# HDMI_Connector_for_RK3399.net
KiCad netlist of a schematic drawn in Altium Designer
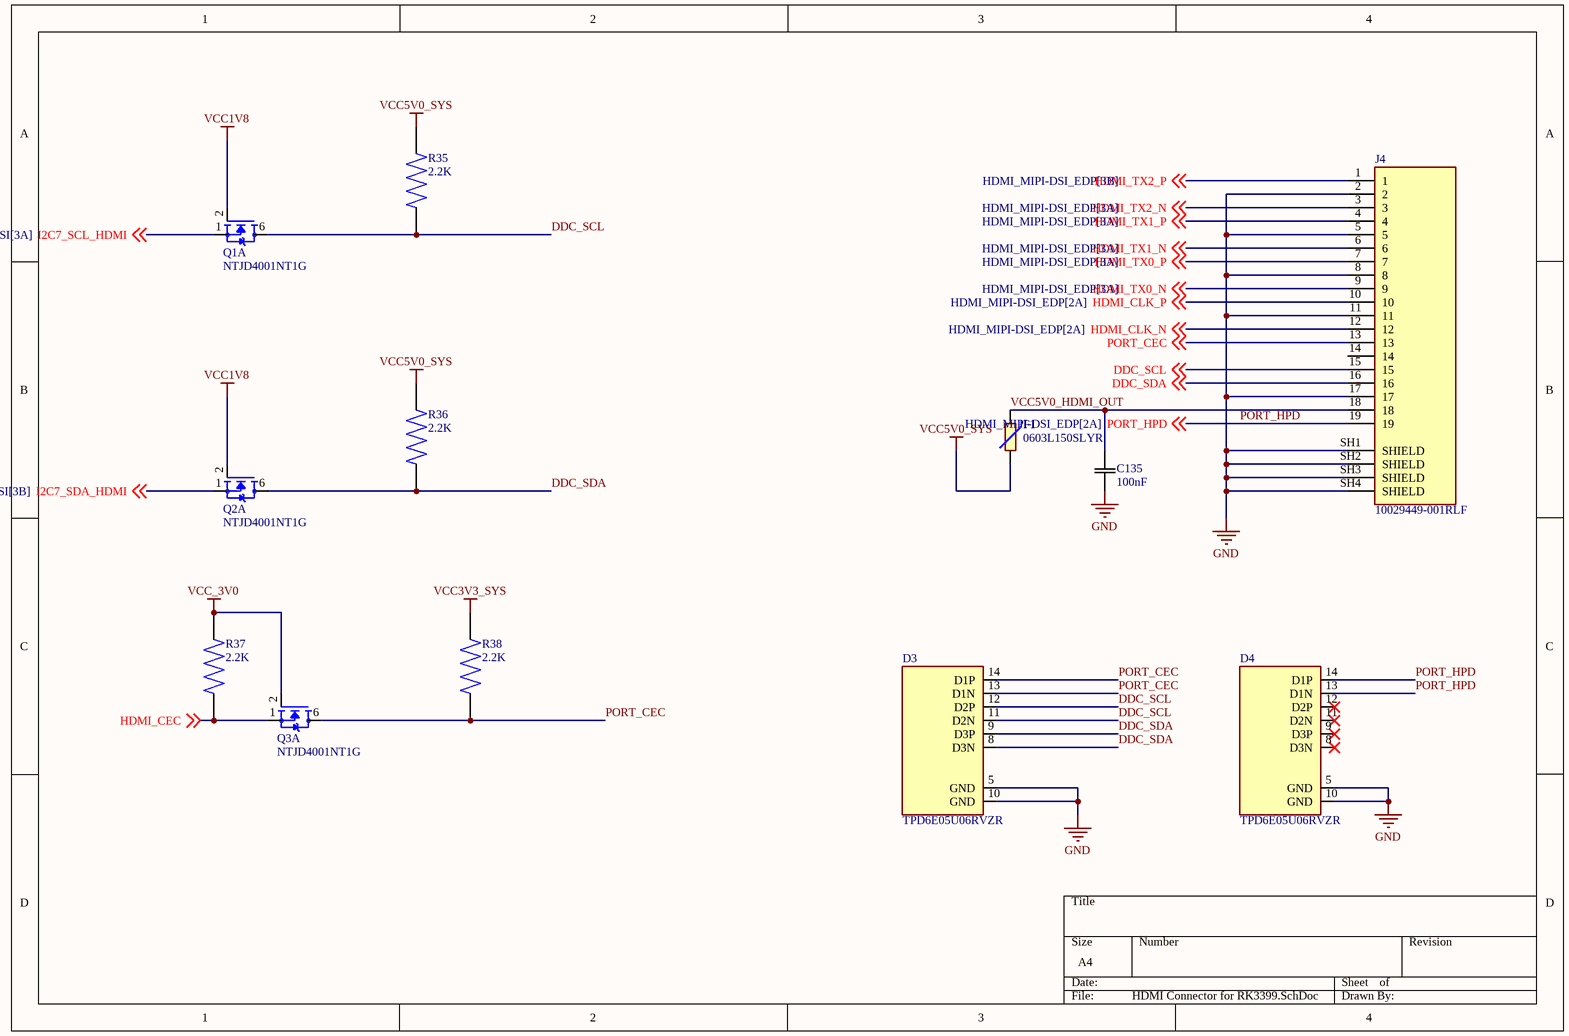
[diagram p0: HDMI Connector for RK3399.SchDoc]

(export (version "E")
  (design (tool "Eeschema 10.0.6"))
  (components
    (comp (ref "C135")
      (value "100nF")
      (footprint "CAP_1005_TDK")
      (description "Description")
      (fields
        (field (name "MANUFACTURER_PART_NUMBER") "C1005X7R1H104M050BB")
        (field (name "COPYRIGHT") "Copyright (C) 2025 Ultra Librarian. All rights reserved.")
      )
      (libsource (lib "C1005X7R1H104M050BB") (part "C1005X7R1H104M050BB"))
    )
    (comp (ref "D3")
      (value "TPD6E05U06RVZR")
      (footprint "SON50P135X350X55-14N")
      (description "6-Channel Ultra low capacitance IEC ESD protection diodes 14-USON -40 to 125")
      (libsource (lib "TPD6E05U06RVZR") (part "TPD6E05U06RVZR"))
    )
    (comp (ref "D4")
      (value "TPD6E05U06RVZR")
      (footprint "SON50P135X350X55-14N")
      (description "6-Channel Ultra low capacitance IEC ESD protection diodes 14-USON -40 to 125")
      (libsource (lib "TPD6E05U06RVZR") (part "TPD6E05U06RVZR"))
    )
    (comp (ref "F1")
      (value "0603L150SLYR")
      (footprint "FUSC1608X100N")
      (description "Polymeric PTC Resettable Fuse 6V 1.5 A Ih Surface Mount 0603 (1608 Metric), Concave")
      (fields (field (name "MF") "Littelfuse Inc."))
      (libsource (lib "0603L150SLYR") (part "0603L150SLYR"))
    )
    (comp (ref "J4")
      (value "10029449-001RLF")
      (footprint "AMPHENOL_10029449-001RLF")
      (libsource (lib "10029449-001RLF") (part "10029449-001RLF"))
    )
    (comp (ref "Q1")
      (value "NTJD4001NT1G")
      (footprint "SOT65P210X110-6N")
      (description "Mosfet Array 2 N-Channel (Dual) 30V 250mA 272mW Surface Mount SC-88/SC70-6/SOT-363")
      (fields (field (name "MF") "ON Semiconductor"))
      (libsource (lib "NTJD4001NT1G") (part "NTJD4001NT1G"))
    )
    (comp (ref "Q2")
      (value "NTJD4001NT1G")
      (footprint "SOT65P210X110-6N")
      (description "Mosfet Array 2 N-Channel (Dual) 30V 250mA 272mW Surface Mount SC-88/SC70-6/SOT-363")
      (fields (field (name "MF") "ON Semiconductor"))
      (libsource (lib "NTJD4001NT1G") (part "NTJD4001NT1G"))
    )
    (comp (ref "Q3")
      (value "NTJD4001NT1G")
      (footprint "SOT65P210X110-6N")
      (description "Mosfet Array 2 N-Channel (Dual) 30V 250mA 272mW Surface Mount SC-88/SC70-6/SOT-363")
      (fields (field (name "MF") "ON Semiconductor"))
      (libsource (lib "NTJD4001NT1G") (part "NTJD4001NT1G"))
    )
    (comp (ref "R35")
      (value "2.2K")
      (footprint "RES_ERA8APB222V")
      (fields (field (name "MP") "ERA8APB222V"))
      (libsource (lib "ERA8APB222V") (part "ERA8APB222V"))
    )
    (comp (ref "R36")
      (value "2.2K")
      (footprint "RES_ERA8APB222V")
      (fields (field (name "MP") "ERA8APB222V"))
      (libsource (lib "ERA8APB222V") (part "ERA8APB222V"))
    )
    (comp (ref "R37")
      (value "2.2K")
      (footprint "RES_ERA8APB222V")
      (fields (field (name "MP") "ERA8APB222V"))
      (libsource (lib "ERA8APB222V") (part "ERA8APB222V"))
    )
    (comp (ref "R38")
      (value "2.2K")
      (footprint "RES_ERA8APB222V")
      (fields (field (name "MP") "ERA8APB222V"))
      (libsource (lib "ERA8APB222V") (part "ERA8APB222V"))
    )
  )
  (nets
    (net (code "1") (name "/VCC5V0_HDMI_OUT") (class "Default")
      (node (ref "C135") (pin "1") (pinfunction "1_1") (pintype "passive"))
      (node (ref "F1") (pin "1") (pinfunction "1_1") (pintype "passive"))
      (node (ref "J4") (pin "18") (pinfunction "18_18") (pintype "passive"))
    )
    (net (code "2") (name "DDC_SCL") (class "Default")
      (node (ref "D3") (pin "11") (pinfunction "D2N_11") (pintype "bidirectional"))
      (node (ref "D3") (pin "12") (pinfunction "D2P_12") (pintype "bidirectional"))
      (node (ref "J4") (pin "15") (pinfunction "15_15") (pintype "passive"))
      (node (ref "Q1") (pin "6") (pinfunction "D1_6") (pintype "passive"))
      (node (ref "R35") (pin "1") (pinfunction "1_1") (pintype "passive"))
    )
    (net (code "3") (name "DDC_SDA") (class "Default")
      (node (ref "D3") (pin "8") (pinfunction "D3N_8") (pintype "bidirectional"))
      (node (ref "D3") (pin "9") (pinfunction "D3P_9") (pintype "bidirectional"))
      (node (ref "J4") (pin "16") (pinfunction "16_16") (pintype "passive"))
      (node (ref "Q2") (pin "6") (pinfunction "D1_6") (pintype "passive"))
      (node (ref "R36") (pin "1") (pinfunction "1_1") (pintype "passive"))
    )
    (net (code "4") (name "GND") (class "Default")
      (node (ref "C135") (pin "2") (pinfunction "2_2") (pintype "passive"))
      (node (ref "D3") (pin "10") (pinfunction "GND_10") (pintype "power_in"))
      (node (ref "D3") (pin "5") (pinfunction "GND_5") (pintype "power_in"))
      (node (ref "D4") (pin "10") (pinfunction "GND_10") (pintype "power_in"))
      (node (ref "D4") (pin "5") (pinfunction "GND_5") (pintype "power_in"))
      (node (ref "J4") (pin "11") (pinfunction "11_11") (pintype "passive"))
      (node (ref "J4") (pin "17") (pinfunction "17_17") (pintype "passive"))
      (node (ref "J4") (pin "2") (pinfunction "2_2") (pintype "passive"))
      (node (ref "J4") (pin "5") (pinfunction "5_5") (pintype "passive"))
      (node (ref "J4") (pin "8") (pinfunction "8_8") (pintype "passive"))
      (node (ref "J4") (pin "SH1") (pinfunction "SHIELD_SH1") (pintype "passive"))
      (node (ref "J4") (pin "SH2") (pinfunction "SHIELD_SH2") (pintype "passive"))
      (node (ref "J4") (pin "SH3") (pinfunction "SHIELD_SH3") (pintype "passive"))
      (node (ref "J4") (pin "SH4") (pinfunction "SHIELD_SH4") (pintype "passive"))
    )
    (net (code "5") (name "HDMI_CEC") (class "Default")
      (node (ref "Q3") (pin "1") (pinfunction "S1_1") (pintype "passive"))
      (node (ref "R37") (pin "1") (pinfunction "1_1") (pintype "passive"))
    )
    (net (code "6") (name "HDMI_CLK_N") (class "Default")
      (node (ref "J4") (pin "12") (pinfunction "12_12") (pintype "passive"))
    )
    (net (code "7") (name "HDMI_CLK_P") (class "Default")
      (node (ref "J4") (pin "10") (pinfunction "10_10") (pintype "passive"))
    )
    (net (code "8") (name "HDMI_TX0_N") (class "Default")
      (node (ref "J4") (pin "9") (pinfunction "9_9") (pintype "passive"))
    )
    (net (code "9") (name "HDMI_TX0_P") (class "Default")
      (node (ref "J4") (pin "7") (pinfunction "7_7") (pintype "passive"))
    )
    (net (code "10") (name "HDMI_TX1_N") (class "Default")
      (node (ref "J4") (pin "6") (pinfunction "6_6") (pintype "passive"))
    )
    (net (code "11") (name "HDMI_TX1_P") (class "Default")
      (node (ref "J4") (pin "4") (pinfunction "4_4") (pintype "passive"))
    )
    (net (code "12") (name "HDMI_TX2_N") (class "Default")
      (node (ref "J4") (pin "3") (pinfunction "3_3") (pintype "passive"))
    )
    (net (code "13") (name "HDMI_TX2_P") (class "Default")
      (node (ref "J4") (pin "1") (pinfunction "1_1") (pintype "passive"))
    )
    (net (code "14") (name "I2C7_SCL_HDMI") (class "Default")
      (node (ref "Q1") (pin "1") (pinfunction "S1_1") (pintype "passive"))
    )
    (net (code "15") (name "I2C7_SDA_HDMI") (class "Default")
      (node (ref "Q2") (pin "1") (pinfunction "S1_1") (pintype "passive"))
    )
    (net (code "16") (name "PORT_CEC") (class "Default")
      (node (ref "D3") (pin "13") (pinfunction "D1N_13") (pintype "bidirectional"))
      (node (ref "D3") (pin "14") (pinfunction "D1P_14") (pintype "bidirectional"))
      (node (ref "J4") (pin "13") (pinfunction "13_13") (pintype "passive"))
      (node (ref "Q3") (pin "6") (pinfunction "D1_6") (pintype "passive"))
      (node (ref "R38") (pin "1") (pinfunction "1_1") (pintype "passive"))
    )
    (net (code "17") (name "PORT_HPD") (class "Default")
      (node (ref "D4") (pin "13") (pinfunction "D1N_13") (pintype "bidirectional"))
      (node (ref "D4") (pin "14") (pinfunction "D1P_14") (pintype "bidirectional"))
      (node (ref "J4") (pin "19") (pinfunction "19_19") (pintype "passive"))
    )
    (net (code "18") (name "VCC1V8") (class "Default")
      (node (ref "Q1") (pin "2") (pinfunction "G1_2") (pintype "passive"))
      (node (ref "Q2") (pin "2") (pinfunction "G1_2") (pintype "passive"))
    )
    (net (code "19") (name "VCC3V3_SYS") (class "Default")
      (node (ref "R38") (pin "2") (pinfunction "2_2") (pintype "passive"))
    )
    (net (code "20") (name "VCC5V0_SYS") (class "Default")
      (node (ref "F1") (pin "2") (pinfunction "2_2") (pintype "passive"))
      (node (ref "R35") (pin "2") (pinfunction "2_2") (pintype "passive"))
      (node (ref "R36") (pin "2") (pinfunction "2_2") (pintype "passive"))
    )
    (net (code "21") (name "VCC_3V0") (class "Default")
      (node (ref "Q3") (pin "2") (pinfunction "G1_2") (pintype "passive"))
      (node (ref "R37") (pin "2") (pinfunction "2_2") (pintype "passive"))
    )
    (net (code "22") (name "unconnected-(D4-D2N-Pad11)") (class "Default")
      (node (ref "D4") (pin "11") (pinfunction "D2N_11") (pintype "bidirectional+no_connect"))
    )
    (net (code "23") (name "unconnected-(D4-D2P-Pad12)") (class "Default")
      (node (ref "D4") (pin "12") (pinfunction "D2P_12") (pintype "bidirectional+no_connect"))
    )
    (net (code "24") (name "unconnected-(D4-D3N-Pad8)") (class "Default")
      (node (ref "D4") (pin "8") (pinfunction "D3N_8") (pintype "bidirectional+no_connect"))
    )
    (net (code "25") (name "unconnected-(D4-D3P-Pad9)") (class "Default")
      (node (ref "D4") (pin "9") (pinfunction "D3P_9") (pintype "bidirectional+no_connect"))
    )
    (net (code "26") (name "unconnected-(J4-Pad14)") (class "Default")
      (node (ref "J4") (pin "14") (pinfunction "14_14") (pintype "passive"))
    )
  )
)
